# IO.net
KiCad netlist of a schematic drawn in Altium Designer
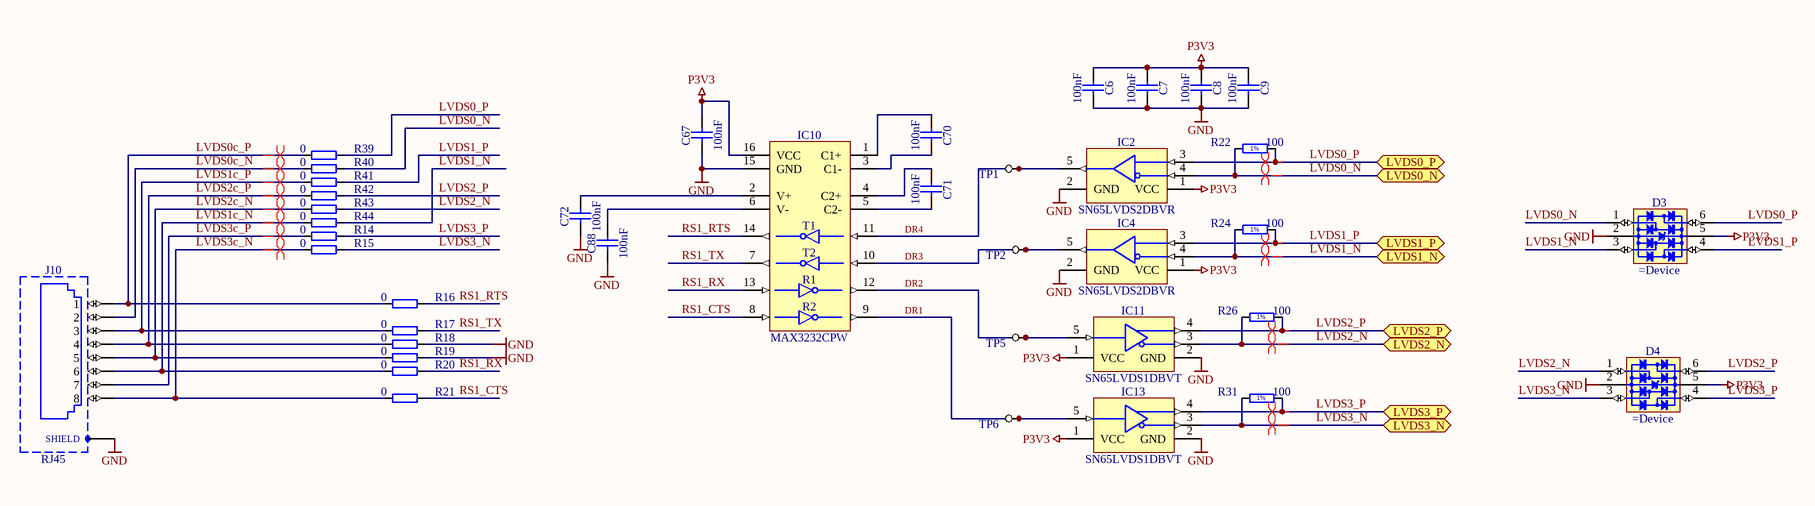
[diagram p0: IO.SchDoc]

(export (version "E")
  (design (tool "Eeschema 10.0.6"))
  (components
    (comp (ref "C6")
      (value "100nF")
      (footprint "CAPC1005X55N")
      (description "Non-polarised capacitor")
      (fields
        (field (name "PART NUMBER") "CC0402_100NF_16V_10%_X5R")
        (field (name "VOLTAGE") "16V")
        (field (name "AUTHOR") "CERN DEM JLC")
      )
      (libsource (lib "Capacitors") (part "Capacitor - non polarized"))
    )
    (comp (ref "C7")
      (value "100nF")
      (footprint "CAPC1005X55N")
      (description "Non-polarised capacitor")
      (fields
        (field (name "PART NUMBER") "CC0402_100NF_16V_10%_X5R")
        (field (name "VOLTAGE") "16V")
        (field (name "AUTHOR") "CERN DEM JLC")
      )
      (libsource (lib "Capacitors") (part "Capacitor - non polarized"))
    )
    (comp (ref "C8")
      (value "100nF")
      (footprint "CAPC1005X55N")
      (description "Non-polarised capacitor")
      (fields
        (field (name "PART NUMBER") "CC0402_100NF_16V_10%_X5R")
        (field (name "VOLTAGE") "16V")
        (field (name "AUTHOR") "CERN DEM JLC")
      )
      (libsource (lib "Capacitors") (part "Capacitor - non polarized"))
    )
    (comp (ref "C9")
      (value "100nF")
      (footprint "CAPC1005X55N")
      (description "Non-polarised capacitor")
      (fields
        (field (name "PART NUMBER") "CC0402_100NF_16V_10%_X5R")
        (field (name "VOLTAGE") "16V")
        (field (name "AUTHOR") "CERN DEM JLC")
      )
      (libsource (lib "Capacitors") (part "Capacitor - non polarized"))
    )
    (comp (ref "C67")
      (value "100nF")
      (footprint "CAPC1005X55N")
      (description "Non-polarised capacitor")
      (fields
        (field (name "PART NUMBER") "CC0402_100NF_16V_10%_X5R")
        (field (name "VOLTAGE") "16V")
        (field (name "AUTHOR") "CERN DEM JLC")
      )
      (libsource (lib "Capacitors") (part "Capacitor - non polarized"))
    )
    (comp (ref "C70")
      (value "100nF")
      (footprint "CAPC1005X55N")
      (description "Non-polarised capacitor")
      (fields
        (field (name "PART NUMBER") "CC0402_100NF_16V_10%_X5R")
        (field (name "VOLTAGE") "16V")
        (field (name "AUTHOR") "CERN DEM JLC")
      )
      (libsource (lib "Capacitors") (part "Capacitor - non polarized"))
    )
    (comp (ref "C71")
      (value "100nF")
      (footprint "CAPC1005X55N")
      (description "Non-polarised capacitor")
      (fields
        (field (name "PART NUMBER") "CC0402_100NF_16V_10%_X5R")
        (field (name "VOLTAGE") "16V")
        (field (name "AUTHOR") "CERN DEM JLC")
      )
      (libsource (lib "Capacitors") (part "Capacitor - non polarized"))
    )
    (comp (ref "C72")
      (value "100nF")
      (footprint "CAPC1005X55N")
      (description "Non-polarised capacitor")
      (fields
        (field (name "PART NUMBER") "CC0402_100NF_16V_10%_X5R")
        (field (name "VOLTAGE") "16V")
        (field (name "AUTHOR") "CERN DEM JLC")
      )
      (libsource (lib "Capacitors") (part "Capacitor - non polarized"))
    )
    (comp (ref "C88")
      (value "100nF")
      (footprint "CAPC1005X55N")
      (description "Non-polarised capacitor")
      (fields
        (field (name "PART NUMBER") "CC0402_100NF_16V_10%_X5R")
        (field (name "VOLTAGE") "16V")
        (field (name "AUTHOR") "CERN DEM JLC")
      )
      (libsource (lib "Capacitors") (part "Capacitor - non polarized"))
    )
    (comp (ref "D3")
      (value "~")
      (footprint "SOTFL50P160X60-6N")
      (fields (field (name "PART NUMBER") "NUP4114UPXV6T1G"))
      (libsource (lib "ICs And Semiconductors") (part "NUP4114"))
    )
    (comp (ref "D4")
      (value "~")
      (footprint "SOTFL50P160X60-6N")
      (fields (field (name "PART NUMBER") "NUP4114UPXV6T1G"))
      (libsource (lib "ICs And Semiconductors") (part "NUP4114"))
    )
    (comp (ref "IC2")
      (value "SN65LVDS2DBVR")
      (footprint "SOT95P280X145-5N")
      (description "High-Speed Differential Line Receiver")
      (fields (field (name "MANUFACTURER") "TEXAS INSTRUMENTS") (field (name "AUTHOR") "CERN DEM JLC"))
      (libsource (lib "ICs And Semiconductors") (part "SN65LVDS2DBV"))
    )
    (comp (ref "IC4")
      (value "SN65LVDS2DBVR")
      (footprint "SOT95P280X145-5N")
      (description "High-Speed Differential Line Receiver")
      (fields (field (name "MANUFACTURER") "TEXAS INSTRUMENTS") (field (name "AUTHOR") "CERN DEM JLC"))
      (libsource (lib "ICs And Semiconductors") (part "SN65LVDS2DBV"))
    )
    (comp (ref "IC10")
      (value "MAX3232CPW")
      (footprint "SOP65P640X120-16N")
      (description "3-V To 5.5-V Multichannel RS-232 Line Driver/Receiver With ±15kV IEC ESD Protection")
      (fields (field (name "MANUFACTURER") "TEXAS INSTRUMENTS") (field (name "AUTHOR") "CERN DEM JLC"))
      (libsource (lib "ICs And Semiconductors") (part "MAX3232CPW"))
    )
    (comp (ref "IC11")
      (value "SN65LVDS1DBVT")
      (footprint "SOT95P280X145-5N")
      (description "High-Speed Differential Line Driver")
      (fields (field (name "MANUFACTURER") "TEXAS INSTRUMENTS") (field (name "AUTHOR") "CERN DEM JLC"))
      (libsource (lib "ICs And Semiconductors") (part "SN65LVDS1DBV"))
    )
    (comp (ref "IC13")
      (value "SN65LVDS1DBVT")
      (footprint "SOT95P280X145-5N")
      (description "High-Speed Differential Line Driver")
      (fields (field (name "MANUFACTURER") "TEXAS INSTRUMENTS") (field (name "AUTHOR") "CERN DEM JLC"))
      (libsource (lib "ICs And Semiconductors") (part "SN65LVDS1DBV"))
    )
    (comp (ref "J10")
      (value "RJ45")
      (footprint "FCI_95678-001LF")
      (description "1 Port, 8 Positions Shielded Snap PEG, CAT5 RJ45 Horizontal Modular Jack")
      (fields
        (field (name "PART NUMBER") "FCI_95678-001LF")
        (field (name "MANUFACTURER") "FCI")
        (field (name "AUTHOR") "CERN DEM BC")
      )
      (libsource (lib "Connectors") (part "FCI_95678-001LF"))
    )
    (comp (ref "R14")
      (value "0")
      (footprint "RESC1005X40N")
      (description "Resistor")
      (fields
        (field (name "PART NUMBER") "R0402_0R_JUMPER")
        (field (name "MANUFACTURER") "GENERIC")
        (field (name "AUTHOR") "CERN DEM JLC")
      )
      (libsource (lib "Resistors") (part "Resistor"))
    )
    (comp (ref "R15")
      (value "0")
      (footprint "RESC1005X40N")
      (description "Resistor")
      (fields
        (field (name "PART NUMBER") "R0402_0R_JUMPER")
        (field (name "MANUFACTURER") "GENERIC")
        (field (name "AUTHOR") "CERN DEM JLC")
      )
      (libsource (lib "Resistors") (part "Resistor"))
    )
    (comp (ref "R16")
      (value "0")
      (footprint "RESC1005X40N")
      (description "Resistor")
      (fields
        (field (name "PART NUMBER") "R0402_0R_JUMPER")
        (field (name "MANUFACTURER") "GENERIC")
        (field (name "AUTHOR") "CERN DEM JLC")
      )
      (libsource (lib "Resistors") (part "Resistor"))
    )
    (comp (ref "R17")
      (value "0")
      (footprint "RESC1005X40N")
      (description "Resistor")
      (fields
        (field (name "PART NUMBER") "R0402_0R_JUMPER")
        (field (name "MANUFACTURER") "GENERIC")
        (field (name "AUTHOR") "CERN DEM JLC")
      )
      (libsource (lib "Resistors") (part "Resistor"))
    )
    (comp (ref "R18")
      (value "0")
      (footprint "RESC1005X40N")
      (description "Resistor")
      (fields
        (field (name "PART NUMBER") "R0402_0R_JUMPER")
        (field (name "MANUFACTURER") "GENERIC")
        (field (name "AUTHOR") "CERN DEM JLC")
      )
      (libsource (lib "Resistors") (part "Resistor"))
    )
    (comp (ref "R19")
      (value "0")
      (footprint "RESC1005X40N")
      (description "Resistor")
      (fields
        (field (name "PART NUMBER") "R0402_0R_JUMPER")
        (field (name "MANUFACTURER") "GENERIC")
        (field (name "AUTHOR") "CERN DEM JLC")
      )
      (libsource (lib "Resistors") (part "Resistor"))
    )
    (comp (ref "R20")
      (value "0")
      (footprint "RESC1005X40N")
      (description "Resistor")
      (fields
        (field (name "PART NUMBER") "R0402_0R_JUMPER")
        (field (name "MANUFACTURER") "GENERIC")
        (field (name "AUTHOR") "CERN DEM JLC")
      )
      (libsource (lib "Resistors") (part "Resistor"))
    )
    (comp (ref "R21")
      (value "0")
      (footprint "RESC1005X40N")
      (description "Resistor")
      (fields
        (field (name "PART NUMBER") "R0402_0R_JUMPER")
        (field (name "MANUFACTURER") "GENERIC")
        (field (name "AUTHOR") "CERN DEM JLC")
      )
      (libsource (lib "Resistors") (part "Resistor"))
    )
    (comp (ref "R22")
      (value "100")
      (footprint "RESC1005X40N")
      (description "Resistor - 1%")
      (fields
        (field (name "PART NUMBER") "R0402_100R_1%_0.0625W_100PPM")
        (field (name "POWER") "0.0625W")
        (field (name "AUTHOR") "CERN DEM JLC")
      )
      (libsource (lib "Resistors") (part "Resistor - 1%"))
    )
    (comp (ref "R24")
      (value "100")
      (footprint "RESC1005X40N")
      (description "Resistor - 1%")
      (fields
        (field (name "PART NUMBER") "R0402_100R_1%_0.0625W_100PPM")
        (field (name "POWER") "0.0625W")
        (field (name "AUTHOR") "CERN DEM JLC")
      )
      (libsource (lib "Resistors") (part "Resistor - 1%"))
    )
    (comp (ref "R26")
      (value "100")
      (footprint "RESC1005X40N")
      (description "Resistor - 1%")
      (fields
        (field (name "PART NUMBER") "R0402_100R_1%_0.0625W_100PPM")
        (field (name "POWER") "0.0625W")
        (field (name "AUTHOR") "CERN DEM JLC")
      )
      (libsource (lib "Resistors") (part "Resistor - 1%"))
    )
    (comp (ref "R31")
      (value "100")
      (footprint "RESC1005X40N")
      (description "Resistor - 1%")
      (fields
        (field (name "PART NUMBER") "R0402_100R_1%_0.0625W_100PPM")
        (field (name "POWER") "0.0625W")
        (field (name "AUTHOR") "CERN DEM JLC")
      )
      (libsource (lib "Resistors") (part "Resistor - 1%"))
    )
    (comp (ref "R39")
      (value "0")
      (footprint "RESC1005X40N")
      (description "Resistor")
      (fields
        (field (name "PART NUMBER") "R0402_0R_JUMPER")
        (field (name "MANUFACTURER") "GENERIC")
        (field (name "AUTHOR") "CERN DEM JLC")
      )
      (libsource (lib "Resistors") (part "Resistor"))
    )
    (comp (ref "R40")
      (value "0")
      (footprint "RESC1005X40N")
      (description "Resistor")
      (fields
        (field (name "PART NUMBER") "R0402_0R_JUMPER")
        (field (name "MANUFACTURER") "GENERIC")
        (field (name "AUTHOR") "CERN DEM JLC")
      )
      (libsource (lib "Resistors") (part "Resistor"))
    )
    (comp (ref "R41")
      (value "0")
      (footprint "RESC1005X40N")
      (description "Resistor")
      (fields
        (field (name "PART NUMBER") "R0402_0R_JUMPER")
        (field (name "MANUFACTURER") "GENERIC")
        (field (name "AUTHOR") "CERN DEM JLC")
      )
      (libsource (lib "Resistors") (part "Resistor"))
    )
    (comp (ref "R42")
      (value "0")
      (footprint "RESC1005X40N")
      (description "Resistor")
      (fields
        (field (name "PART NUMBER") "R0402_0R_JUMPER")
        (field (name "MANUFACTURER") "GENERIC")
        (field (name "AUTHOR") "CERN DEM JLC")
      )
      (libsource (lib "Resistors") (part "Resistor"))
    )
    (comp (ref "R43")
      (value "0")
      (footprint "RESC1005X40N")
      (description "Resistor")
      (fields
        (field (name "PART NUMBER") "R0402_0R_JUMPER")
        (field (name "MANUFACTURER") "GENERIC")
        (field (name "AUTHOR") "CERN DEM JLC")
      )
      (libsource (lib "Resistors") (part "Resistor"))
    )
    (comp (ref "R44")
      (value "0")
      (footprint "RESC1005X40N")
      (description "Resistor")
      (fields
        (field (name "PART NUMBER") "R0402_0R_JUMPER")
        (field (name "MANUFACTURER") "GENERIC")
        (field (name "AUTHOR") "CERN DEM JLC")
      )
      (libsource (lib "Resistors") (part "Resistor"))
    )
    (comp (ref "TP1")
      (value "TP")
      (footprint "TP")
      (description "Testpoint")
      (libsource (lib "LIBRARY_SCH") (part "TP"))
    )
    (comp (ref "TP2")
      (value "TP")
      (footprint "TP")
      (description "Testpoint")
      (libsource (lib "LIBRARY_SCH") (part "TP"))
    )
    (comp (ref "TP5")
      (value "TP")
      (footprint "TP")
      (description "Testpoint")
      (libsource (lib "LIBRARY_SCH") (part "TP"))
    )
    (comp (ref "TP6")
      (value "TP")
      (footprint "TP")
      (description "Testpoint")
      (libsource (lib "LIBRARY_SCH") (part "TP"))
    )
  )
  (nets
    (net (code "1") (name "/DR1") (class "Default")
      (node (ref "IC10") (pin "9") (pinfunction "R2OUT_9") (pintype "output"))
      (node (ref "IC13") (pin "5") (pinfunction "R_5") (pintype "input"))
      (node (ref "TP6") (pin "1") (pintype "passive"))
    )
    (net (code "2") (name "/DR2") (class "Default")
      (node (ref "IC10") (pin "12") (pinfunction "R1OUT_12") (pintype "output"))
      (node (ref "IC11") (pin "5") (pinfunction "R_5") (pintype "input"))
      (node (ref "TP5") (pin "1") (pintype "passive"))
    )
    (net (code "3") (name "/DR3") (class "Default")
      (node (ref "IC10") (pin "10") (pinfunction "T2IN_10") (pintype "input"))
      (node (ref "IC4") (pin "5") (pinfunction "R_5") (pintype "output"))
      (node (ref "TP2") (pin "1") (pintype "passive"))
    )
    (net (code "4") (name "/DR4") (class "Default")
      (node (ref "IC10") (pin "11") (pinfunction "T1IN_11") (pintype "input"))
      (node (ref "IC2") (pin "5") (pinfunction "R_5") (pintype "output"))
      (node (ref "TP1") (pin "1") (pintype "passive"))
    )
    (net (code "5") (name "/LVDS0_N") (class "Default")
      (node (ref "D3") (pin "1") (pinfunction "I/O1_1") (pintype "bidirectional"))
      (node (ref "IC2") (pin "4") (pinfunction "B_4") (pintype "input"))
      (node (ref "R22") (pin "1") (pinfunction "1_1") (pintype "passive"))
      (node (ref "R40") (pin "2") (pinfunction "2_2") (pintype "passive"))
    )
    (net (code "6") (name "/LVDS0_P") (class "Default")
      (node (ref "D3") (pin "6") (pinfunction "I/O4_6") (pintype "bidirectional"))
      (node (ref "IC2") (pin "3") (pinfunction "A_3") (pintype "input"))
      (node (ref "R22") (pin "2") (pinfunction "2_2") (pintype "passive"))
      (node (ref "R39") (pin "2") (pinfunction "2_2") (pintype "passive"))
    )
    (net (code "7") (name "/LVDS0c_N") (class "Default")
      (node (ref "J10") (pin "2") (pinfunction "2_2") (pintype "bidirectional"))
      (node (ref "R40") (pin "1") (pinfunction "1_1") (pintype "passive"))
    )
    (net (code "8") (name "/LVDS0c_P") (class "Default")
      (node (ref "J10") (pin "1") (pinfunction "1_1") (pintype "bidirectional"))
      (node (ref "R16") (pin "1") (pinfunction "1_1") (pintype "passive"))
      (node (ref "R39") (pin "1") (pinfunction "1_1") (pintype "passive"))
    )
    (net (code "9") (name "/LVDS1_N") (class "Default")
      (node (ref "D3") (pin "3") (pinfunction "I/O2_3") (pintype "bidirectional"))
      (node (ref "IC4") (pin "4") (pinfunction "B_4") (pintype "input"))
      (node (ref "R24") (pin "1") (pinfunction "1_1") (pintype "passive"))
      (node (ref "R44") (pin "2") (pinfunction "2_2") (pintype "passive"))
    )
    (net (code "10") (name "/LVDS1_P") (class "Default")
      (node (ref "D3") (pin "4") (pinfunction "I/O3_4") (pintype "bidirectional"))
      (node (ref "IC4") (pin "3") (pinfunction "A_3") (pintype "input"))
      (node (ref "R24") (pin "2") (pinfunction "2_2") (pintype "passive"))
      (node (ref "R41") (pin "2") (pinfunction "2_2") (pintype "passive"))
    )
    (net (code "11") (name "/LVDS1c_N") (class "Default")
      (node (ref "J10") (pin "6") (pinfunction "6_6") (pintype "bidirectional"))
      (node (ref "R20") (pin "1") (pinfunction "1_1") (pintype "passive"))
      (node (ref "R44") (pin "1") (pinfunction "1_1") (pintype "passive"))
    )
    (net (code "12") (name "/LVDS1c_P") (class "Default")
      (node (ref "J10") (pin "3") (pinfunction "3_3") (pintype "bidirectional"))
      (node (ref "R17") (pin "1") (pinfunction "1_1") (pintype "passive"))
      (node (ref "R41") (pin "1") (pinfunction "1_1") (pintype "passive"))
    )
    (net (code "13") (name "/LVDS2_N") (class "Default")
      (node (ref "D4") (pin "1") (pinfunction "I/O1_1") (pintype "bidirectional"))
      (node (ref "IC11") (pin "3") (pinfunction "A_3") (pintype "output"))
      (node (ref "R26") (pin "1") (pinfunction "1_1") (pintype "passive"))
      (node (ref "R43") (pin "2") (pinfunction "2_2") (pintype "passive"))
    )
    (net (code "14") (name "/LVDS2_P") (class "Default")
      (node (ref "D4") (pin "6") (pinfunction "I/O4_6") (pintype "bidirectional"))
      (node (ref "IC11") (pin "4") (pinfunction "B_4") (pintype "output"))
      (node (ref "R26") (pin "2") (pinfunction "2_2") (pintype "passive"))
      (node (ref "R42") (pin "2") (pinfunction "2_2") (pintype "passive"))
    )
    (net (code "15") (name "/LVDS2c_N") (class "Default")
      (node (ref "J10") (pin "5") (pinfunction "5_5") (pintype "bidirectional"))
      (node (ref "R19") (pin "1") (pinfunction "1_1") (pintype "passive"))
      (node (ref "R43") (pin "1") (pinfunction "1_1") (pintype "passive"))
    )
    (net (code "16") (name "/LVDS2c_P") (class "Default")
      (node (ref "J10") (pin "4") (pinfunction "4_4") (pintype "bidirectional"))
      (node (ref "R18") (pin "1") (pinfunction "1_1") (pintype "passive"))
      (node (ref "R42") (pin "1") (pinfunction "1_1") (pintype "passive"))
    )
    (net (code "17") (name "/LVDS3_N") (class "Default")
      (node (ref "D4") (pin "3") (pinfunction "I/O2_3") (pintype "bidirectional"))
      (node (ref "IC13") (pin "3") (pinfunction "A_3") (pintype "output"))
      (node (ref "R15") (pin "2") (pinfunction "2_2") (pintype "passive"))
      (node (ref "R31") (pin "1") (pinfunction "1_1") (pintype "passive"))
    )
    (net (code "18") (name "/LVDS3_P") (class "Default")
      (node (ref "D4") (pin "4") (pinfunction "I/O3_4") (pintype "bidirectional"))
      (node (ref "IC13") (pin "4") (pinfunction "B_4") (pintype "output"))
      (node (ref "R14") (pin "2") (pinfunction "2_2") (pintype "passive"))
      (node (ref "R31") (pin "2") (pinfunction "2_2") (pintype "passive"))
    )
    (net (code "19") (name "/LVDS3c_N") (class "Default")
      (node (ref "J10") (pin "8") (pinfunction "8_8") (pintype "bidirectional"))
      (node (ref "R15") (pin "1") (pinfunction "1_1") (pintype "passive"))
      (node (ref "R21") (pin "1") (pinfunction "1_1") (pintype "passive"))
    )
    (net (code "20") (name "/LVDS3c_P") (class "Default")
      (node (ref "J10") (pin "7") (pinfunction "7_7") (pintype "bidirectional"))
      (node (ref "R14") (pin "1") (pinfunction "1_1") (pintype "passive"))
    )
    (net (code "21") (name "/RS1_CTS") (class "Default")
      (node (ref "IC10") (pin "8") (pinfunction "R2IN_8") (pintype "input"))
      (node (ref "R21") (pin "2") (pinfunction "2_2") (pintype "passive"))
    )
    (net (code "22") (name "/RS1_RTS") (class "Default")
      (node (ref "IC10") (pin "14") (pinfunction "T1OUT_14") (pintype "output"))
      (node (ref "R16") (pin "2") (pinfunction "2_2") (pintype "passive"))
    )
    (net (code "23") (name "/RS1_RX") (class "Default")
      (node (ref "IC10") (pin "13") (pinfunction "R1IN_13") (pintype "input"))
      (node (ref "R20") (pin "2") (pinfunction "2_2") (pintype "passive"))
    )
    (net (code "24") (name "/RS1_TX") (class "Default")
      (node (ref "IC10") (pin "7") (pinfunction "T2OUT_7") (pintype "output"))
      (node (ref "R17") (pin "2") (pinfunction "2_2") (pintype "passive"))
    )
    (net (code "25") (name "GND") (class "Default")
      (node (ref "C6") (pin "1") (pinfunction "1_1") (pintype "passive"))
      (node (ref "C67") (pin "1") (pinfunction "1_1") (pintype "passive"))
      (node (ref "C7") (pin "1") (pinfunction "1_1") (pintype "passive"))
      (node (ref "C72") (pin "2") (pinfunction "2_2") (pintype "passive"))
      (node (ref "C8") (pin "1") (pinfunction "1_1") (pintype "passive"))
      (node (ref "C88") (pin "2") (pinfunction "2_2") (pintype "passive"))
      (node (ref "C9") (pin "1") (pinfunction "1_1") (pintype "passive"))
      (node (ref "D3") (pin "2") (pinfunction "GND_2") (pintype "power_in"))
      (node (ref "D4") (pin "2") (pinfunction "GND_2") (pintype "power_in"))
      (node (ref "IC10") (pin "15") (pinfunction "GND_15") (pintype "power_in"))
      (node (ref "IC11") (pin "2") (pinfunction "GND_2") (pintype "power_in"))
      (node (ref "IC13") (pin "2") (pinfunction "GND_2") (pintype "power_in"))
      (node (ref "IC2") (pin "2") (pinfunction "GND_2") (pintype "power_in"))
      (node (ref "IC4") (pin "2") (pinfunction "GND_2") (pintype "power_in"))
      (node (ref "J10") (pin "SHIELD") (pinfunction "SHIELD_SHIELD") (pintype "passive"))
      (node (ref "R18") (pin "2") (pinfunction "2_2") (pintype "passive"))
      (node (ref "R19") (pin "2") (pinfunction "2_2") (pintype "passive"))
    )
    (net (code "26") (name "Net-(IC10-C1+)") (class "Default")
      (node (ref "C70") (pin "2") (pinfunction "2_2") (pintype "passive"))
      (node (ref "IC10") (pin "1") (pinfunction "C1+_1") (pintype "passive"))
    )
    (net (code "27") (name "Net-(IC10-C1-)") (class "Default")
      (node (ref "C70") (pin "1") (pinfunction "1_1") (pintype "passive"))
      (node (ref "IC10") (pin "3") (pinfunction "C1-_3") (pintype "passive"))
    )
    (net (code "28") (name "Net-(IC10-C2+)") (class "Default")
      (node (ref "C71") (pin "2") (pinfunction "2_2") (pintype "passive"))
      (node (ref "IC10") (pin "4") (pinfunction "C2+_4") (pintype "passive"))
    )
    (net (code "29") (name "Net-(IC10-C2-)") (class "Default")
      (node (ref "C71") (pin "1") (pinfunction "1_1") (pintype "passive"))
      (node (ref "IC10") (pin "5") (pinfunction "C2-_5") (pintype "passive"))
    )
    (net (code "30") (name "Net-(IC10-V+)") (class "Default")
      (node (ref "C72") (pin "1") (pinfunction "1_1") (pintype "passive"))
      (node (ref "IC10") (pin "2") (pinfunction "V+_2") (pintype "power_in"))
    )
    (net (code "31") (name "Net-(IC10-V-)") (class "Default")
      (node (ref "C88") (pin "1") (pinfunction "1_1") (pintype "passive"))
      (node (ref "IC10") (pin "6") (pinfunction "V-_6") (pintype "power_in"))
    )
    (net (code "32") (name "P3V3") (class "Default")
      (node (ref "C6") (pin "2") (pinfunction "2_2") (pintype "passive"))
      (node (ref "C67") (pin "2") (pinfunction "2_2") (pintype "passive"))
      (node (ref "C7") (pin "2") (pinfunction "2_2") (pintype "passive"))
      (node (ref "C8") (pin "2") (pinfunction "2_2") (pintype "passive"))
      (node (ref "C9") (pin "2") (pinfunction "2_2") (pintype "passive"))
      (node (ref "D3") (pin "5") (pinfunction "VBUS_5") (pintype "power_in"))
      (node (ref "D4") (pin "5") (pinfunction "VBUS_5") (pintype "power_in"))
      (node (ref "IC10") (pin "16") (pinfunction "VCC_16") (pintype "power_in"))
      (node (ref "IC11") (pin "1") (pinfunction "VCC_1") (pintype "power_in"))
      (node (ref "IC13") (pin "1") (pinfunction "VCC_1") (pintype "power_in"))
      (node (ref "IC2") (pin "1") (pinfunction "VCC_1") (pintype "power_in"))
      (node (ref "IC4") (pin "1") (pinfunction "VCC_1") (pintype "power_in"))
    )
  )
)
